# 3_waffling60-ALPS_mcu.net
KiCad netlist of a schematic drawn in Altium Designer
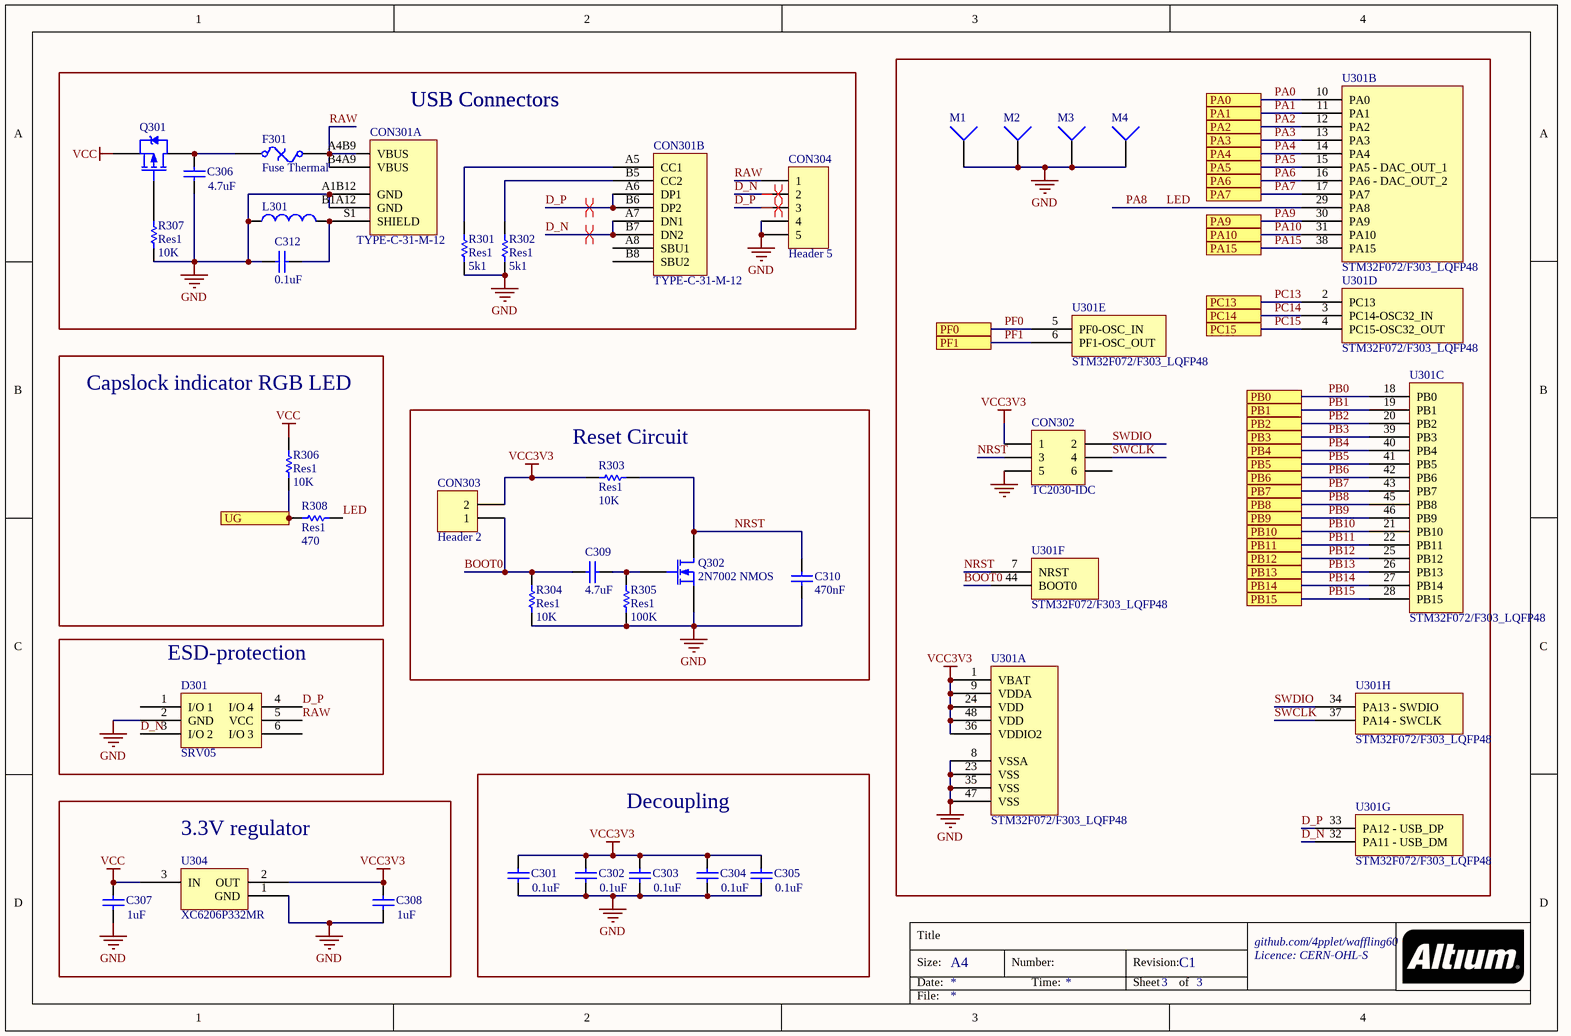
[diagram p0: 3_waffling60-ALPS_mcu.SchDoc]

(export (version "E")
  (design (tool "Eeschema 10.0.6"))
  (components
    (comp (ref "C301")
      (value "0.1uF")
      (footprint "C0603[1608]")
      (description "Capacitor")
      (fields (field (name "LCSC PART #") "C14663") (field (name "MRF.PART") "CC0603KRX7R9BB104"))
      (libsource (lib "Miscellaneous Devices") (part "Cap"))
    )
    (comp (ref "C302")
      (value "0.1uF")
      (footprint "C0603[1608]")
      (description "Capacitor")
      (fields (field (name "LCSC PART #") "C14663") (field (name "MRF.PART") "CC0603KRX7R9BB104"))
      (libsource (lib "Miscellaneous Devices") (part "Cap"))
    )
    (comp (ref "C303")
      (value "0.1uF")
      (footprint "C0603[1608]")
      (description "Capacitor")
      (fields (field (name "LCSC PART #") "C14663") (field (name "MRF.PART") "CC0603KRX7R9BB104"))
      (libsource (lib "Miscellaneous Devices") (part "Cap"))
    )
    (comp (ref "C304")
      (value "0.1uF")
      (footprint "C0603[1608]")
      (description "Capacitor")
      (fields (field (name "LCSC PART #") "C14663") (field (name "MRF.PART") "CC0603KRX7R9BB104"))
      (libsource (lib "Miscellaneous Devices") (part "Cap"))
    )
    (comp (ref "C305")
      (value "0.1uF")
      (footprint "C0603[1608]")
      (description "Capacitor")
      (fields (field (name "LCSC PART #") "C14663") (field (name "MRF.PART") "CC0603KRX7R9BB104"))
      (libsource (lib "Miscellaneous Devices") (part "Cap"))
    )
    (comp (ref "C306")
      (value "4.7uF")
      (footprint "C0603[1608]")
      (description "Capacitor")
      (fields (field (name "LCSC PART #") "C19666") (field (name "MRF.PART") "CL10A475KO8NNNC"))
      (libsource (lib "Miscellaneous Devices") (part "Cap"))
    )
    (comp (ref "C307")
      (value "1uF")
      (footprint "C0603[1608]")
      (description "Capacitor")
      (fields (field (name "LCSC PART #") "C15849") (field (name "MRF.PART") "CL10A105KB8NNNC"))
      (libsource (lib "Miscellaneous Devices") (part "Cap"))
    )
    (comp (ref "C308")
      (value "1uF")
      (footprint "C0603[1608]")
      (description "Capacitor")
      (fields (field (name "LCSC PART #") "C15849") (field (name "MRF.PART") "CL10A105KB8NNNC"))
      (libsource (lib "Miscellaneous Devices") (part "Cap"))
    )
    (comp (ref "C309")
      (value "4.7uF")
      (footprint "C0603[1608]")
      (description "Capacitor")
      (fields (field (name "LCSC PART #") "C19666") (field (name "MRF.PART") "CL10A475KO8NNNC"))
      (libsource (lib "Miscellaneous Devices") (part "Cap"))
    )
    (comp (ref "C310")
      (value "470nF")
      (footprint "C0603[1608]")
      (description "Capacitor")
      (fields (field (name "LCSC PART #") "C1623") (field (name "MRF.PART") "CL10B474KA8NNNC"))
      (libsource (lib "Miscellaneous Devices") (part "Cap"))
    )
    (comp (ref "C312")
      (value "0.1uF")
      (footprint "C0603[1608]")
      (description "Capacitor")
      (fields (field (name "LCSC PART #") "C14663") (field (name "MRF.PART") "CC0603KRX7R9BB104"))
      (libsource (lib "Miscellaneous Devices") (part "Cap"))
    )
    (comp (ref "CON301")
      (value "TYPE-C-31-M-12")
      (footprint "TYPE-C-31-M-12")
      (fields (field (name "LCSC PART #") "C165948"))
      (libsource (lib "Schlib1") (part "TYPE-C-31-M-12"))
    )
    (comp (ref "CON302")
      (value "TC2030-IDC")
      (footprint "TC2030-IDC-NL")
      (description "Header, 3-Pin, Dual row")
      (libsource (lib "Miscellaneous Connectors") (part "Header 3X2"))
    )
    (comp (ref "CON303")
      (value "Header 2")
      (footprint "HDR1X2")
      (description "Header, 2-Pin")
      (libsource (lib "Miscellaneous Connectors") (part "Header 2"))
    )
    (comp (ref "CON304")
      (value "Header 5")
      (footprint "UDB_combo_JST_MOLEX")
      (description "JST for USB daughter board")
      (fields (field (name "LCSC PART #") "C145956"))
      (libsource (lib "Miscellaneous Connectors") (part "Header 5"))
    )
    (comp (ref "D301")
      (value "SRV05")
      (footprint "SOT-23-6")
      (fields (field (name "LCSC PART #") "C85364") (field (name "MRF.PART") "SRV05-4-P-T7"))
      (libsource (lib "Keebs") (part "SRV05"))
    )
    (comp (ref "F301")
      (value "Fuse Thermal")
      (footprint "C1206[3216]")
      (description "Thermal Fuse")
      (fields (field (name "LCSC PART #") "C135338") (field (name "MRF.PART") "ASMD1206-050"))
      (libsource (lib "Miscellaneous Devices") (part "Fuse Thermal"))
    )
    (comp (ref "L301")
      (value "Inductor")
      (footprint "L0805")
      (fields (field (name "LCSC PART #") "C1015") (field (name "MRF.PART") "GZ2012D101TF"))
      (libsource (lib "Simulation Generic Components") (part "Inductor"))
    )
    (comp (ref "M1")
      (value "Socket")
      (footprint "mounting_hole")
      (libsource (lib "Miscellaneous Connectors") (part "Socket"))
    )
    (comp (ref "M2")
      (value "Socket")
      (footprint "mounting_hole")
      (libsource (lib "Miscellaneous Connectors") (part "Socket"))
    )
    (comp (ref "M3")
      (value "Socket")
      (footprint "mounting_hole")
      (libsource (lib "Miscellaneous Connectors") (part "Socket"))
    )
    (comp (ref "M4")
      (value "Socket")
      (footprint "mounting_hole")
      (libsource (lib "Miscellaneous Connectors") (part "Socket"))
    )
    (comp (ref "Q301")
      (value "PMOS-2")
      (footprint "SOT-23-3")
      (description "P-Channel Power MOSFET")
      (fields (field (name "LCSC PART #") "C10487") (field (name "MRF.PART") "SI2301CDS-T1-GE3"))
      (libsource (lib "Miscellaneous Devices") (part "PMOS-2"))
    )
    (comp (ref "Q302")
      (value "2N7002 NMOS")
      (footprint "SOT-23-3")
      (description "N-Channel MOSFET")
      (fields (field (name "LCSC PART #") "C8545") (field (name "MRF.PART") "2N7002"))
      (libsource (lib "Miscellaneous Devices") (part "MOSFET-N"))
    )
    (comp (ref "R301")
      (value "Res1")
      (footprint "R0603[1608]")
      (description "Resistor")
      (fields
        (field (name "ALTIUM_VALUE") "5k1")
        (field (name "LCSC PART #") "C23186")
        (field (name "MRF.PART") "0603WAF5101T5E")
      )
      (libsource (lib "Miscellaneous Devices") (part "Res1"))
    )
    (comp (ref "R302")
      (value "Res1")
      (footprint "R0603[1608]")
      (description "Resistor")
      (fields
        (field (name "ALTIUM_VALUE") "5k1")
        (field (name "LCSC PART #") "C23186")
        (field (name "MRF.PART") "0603WAF5101T5E")
      )
      (libsource (lib "Miscellaneous Devices") (part "Res1"))
    )
    (comp (ref "R303")
      (value "Res1")
      (footprint "R0603[1608]")
      (description "Resistor")
      (fields
        (field (name "ALTIUM_VALUE") "10K")
        (field (name "LCSC PART #") "C25804")
        (field (name "MRF.PART") "0603WAF1002T5E")
      )
      (libsource (lib "Miscellaneous Devices") (part "Res1"))
    )
    (comp (ref "R304")
      (value "Res1")
      (footprint "R0603[1608]")
      (description "Resistor")
      (fields
        (field (name "ALTIUM_VALUE") "10K")
        (field (name "LCSC PART #") "C25804")
        (field (name "MRF.PART") "0603WAF1002T5E")
      )
      (libsource (lib "Miscellaneous Devices") (part "Res1"))
    )
    (comp (ref "R305")
      (value "Res1")
      (footprint "R0603[1608]")
      (description "Resistor")
      (fields
        (field (name "ALTIUM_VALUE") "100K")
        (field (name "LCSC PART #") "C25803")
        (field (name "MRF.PART") "0603WAF1003T5E")
      )
      (libsource (lib "Miscellaneous Devices") (part "Res1"))
    )
    (comp (ref "R306")
      (value "Res1")
      (footprint "R0603[1608]")
      (description "Resistor")
      (fields
        (field (name "ALTIUM_VALUE") "10K")
        (field (name "LCSC PART #") "C25804")
        (field (name "MRF.PART") "0603WAF1002T5E")
      )
      (libsource (lib "Miscellaneous Devices") (part "Res1"))
    )
    (comp (ref "R307")
      (value "Res1")
      (footprint "R0603[1608]")
      (description "Resistor")
      (fields
        (field (name "ALTIUM_VALUE") "10K")
        (field (name "LCSC PART #") "C25804")
        (field (name "MRF.PART") "0603WAF1002T5E")
      )
      (libsource (lib "Miscellaneous Devices") (part "Res1"))
    )
    (comp (ref "R308")
      (value "Res1")
      (footprint "R0603[1608]")
      (description "Resistor")
      (fields
        (field (name "ALTIUM_VALUE") "470")
        (field (name "LCSC PART #") "C23179")
        (field (name "MRF.PART") "0603WAF4700T5E")
      )
      (libsource (lib "Miscellaneous Devices") (part "Res1"))
    )
    (comp (ref "U301")
      (value "STM32F072/F303_LQFP48")
      (footprint "STM32 - COMBO 7X7MM")
      (fields (field (name "LCSC PART #") "C915660") (field (name "MRF.PART") "APM32F072CBT6"))
      (libsource (lib "Keebs") (part "STM32F072/F303_LQFP48"))
    )
    (comp (ref "U304")
      (value "XC6206P332MR")
      (footprint "SOT-23-3")
      (fields (field (name "LCSC PART #") "C5446"))
      (libsource (lib "Keebs") (part "SOT23 LDO"))
    )
  )
  (nets
    (net (code "1") (name "/BOOT0") (class "Default")
      (node (ref "C309") (pin "1") (pinfunction "1_1") (pintype "passive"))
      (node (ref "CON303") (pin "1") (pinfunction "1_1") (pintype "passive"))
      (node (ref "R304") (pin "1") (pinfunction "1_1") (pintype "passive"))
      (node (ref "U301") (pin "44") (pinfunction "BOOT0_44") (pintype "passive"))
    )
    (net (code "2") (name "/D_N") (class "Default")
      (node (ref "CON301") (pin "A7") (pinfunction "DN1_A7") (pintype "passive"))
      (node (ref "CON301") (pin "B7") (pinfunction "DN2_B7") (pintype "passive"))
      (node (ref "CON304") (pin "2") (pinfunction "2_2") (pintype "passive"))
      (node (ref "D301") (pin "3") (pinfunction "I/O_2_3") (pintype "passive"))
      (node (ref "U301") (pin "32") (pinfunction "PA11_-_USB_DM_32") (pintype "passive"))
    )
    (net (code "3") (name "/D_P") (class "Default")
      (node (ref "CON301") (pin "A6") (pinfunction "DP1_A6") (pintype "passive"))
      (node (ref "CON301") (pin "B6") (pinfunction "DP2_B6") (pintype "passive"))
      (node (ref "CON304") (pin "3") (pinfunction "3_3") (pintype "passive"))
      (node (ref "D301") (pin "4") (pinfunction "I/O_4_4") (pintype "passive"))
      (node (ref "U301") (pin "33") (pinfunction "PA12_-_USB_DP_33") (pintype "passive"))
    )
    (net (code "4") (name "/LED") (class "Default")
      (node (ref "R308") (pin "2") (pinfunction "2_2") (pintype "passive"))
      (node (ref "U301") (pin "29") (pinfunction "PA8_29") (pintype "passive"))
    )
    (net (code "5") (name "/NRST") (class "Default")
      (node (ref "C310") (pin "1") (pinfunction "1_1") (pintype "passive"))
      (node (ref "CON302") (pin "3") (pinfunction "3_3") (pintype "passive"))
      (node (ref "Q302") (pin "3") (pinfunction "D_3") (pintype "passive"))
      (node (ref "R303") (pin "2") (pinfunction "2_2") (pintype "passive"))
      (node (ref "U301") (pin "7") (pinfunction "NRST_7") (pintype "passive"))
    )
    (net (code "6") (name "/PA0") (class "Default")
      (node (ref "U301") (pin "10") (pinfunction "PA0_10") (pintype "passive"))
    )
    (net (code "7") (name "/PA1") (class "Default")
      (node (ref "U301") (pin "11") (pinfunction "PA1_11") (pintype "passive"))
    )
    (net (code "8") (name "/PA2") (class "Default")
      (node (ref "U301") (pin "12") (pinfunction "PA2_12") (pintype "passive"))
    )
    (net (code "9") (name "/PA3") (class "Default")
      (node (ref "U301") (pin "13") (pinfunction "PA3_13") (pintype "passive"))
    )
    (net (code "10") (name "/PA4") (class "Default")
      (node (ref "U301") (pin "14") (pinfunction "PA4_14") (pintype "passive"))
    )
    (net (code "11") (name "/PA5") (class "Default")
      (node (ref "U301") (pin "15") (pinfunction "PA5_-_DAC_OUT_1_15") (pintype "passive"))
    )
    (net (code "12") (name "/PA6") (class "Default")
      (node (ref "U301") (pin "16") (pinfunction "PA6_-_DAC_OUT_2_16") (pintype "passive"))
    )
    (net (code "13") (name "/PA7") (class "Default")
      (node (ref "U301") (pin "17") (pinfunction "PA7_17") (pintype "passive"))
    )
    (net (code "14") (name "/PA9") (class "Default")
      (node (ref "U301") (pin "30") (pinfunction "PA9_30") (pintype "passive"))
    )
    (net (code "15") (name "/PA10") (class "Default")
      (node (ref "U301") (pin "31") (pinfunction "PA10_31") (pintype "passive"))
    )
    (net (code "16") (name "/PA15") (class "Default")
      (node (ref "U301") (pin "38") (pinfunction "PA15_38") (pintype "passive"))
    )
    (net (code "17") (name "/PB0") (class "Default")
      (node (ref "U301") (pin "18") (pinfunction "PB0_18") (pintype "passive"))
    )
    (net (code "18") (name "/PB1") (class "Default")
      (node (ref "U301") (pin "19") (pinfunction "PB1_19") (pintype "passive"))
    )
    (net (code "19") (name "/PB2") (class "Default")
      (node (ref "U301") (pin "20") (pinfunction "PB2_20") (pintype "passive"))
    )
    (net (code "20") (name "/PB3") (class "Default")
      (node (ref "U301") (pin "39") (pinfunction "PB3_39") (pintype "passive"))
    )
    (net (code "21") (name "/PB4") (class "Default")
      (node (ref "U301") (pin "40") (pinfunction "PB4_40") (pintype "passive"))
    )
    (net (code "22") (name "/PB5") (class "Default")
      (node (ref "U301") (pin "41") (pinfunction "PB5_41") (pintype "passive"))
    )
    (net (code "23") (name "/PB6") (class "Default")
      (node (ref "U301") (pin "42") (pinfunction "PB6_42") (pintype "passive"))
    )
    (net (code "24") (name "/PB7") (class "Default")
      (node (ref "U301") (pin "43") (pinfunction "PB7_43") (pintype "passive"))
    )
    (net (code "25") (name "/PB8") (class "Default")
      (node (ref "U301") (pin "45") (pinfunction "PB8_45") (pintype "passive"))
    )
    (net (code "26") (name "/PB9") (class "Default")
      (node (ref "U301") (pin "46") (pinfunction "PB9_46") (pintype "passive"))
    )
    (net (code "27") (name "/PB10") (class "Default")
      (node (ref "U301") (pin "21") (pinfunction "PB10_21") (pintype "passive"))
    )
    (net (code "28") (name "/PB11") (class "Default")
      (node (ref "U301") (pin "22") (pinfunction "PB11_22") (pintype "passive"))
    )
    (net (code "29") (name "/PB12") (class "Default")
      (node (ref "U301") (pin "25") (pinfunction "PB12_25") (pintype "passive"))
    )
    (net (code "30") (name "/PB13") (class "Default")
      (node (ref "U301") (pin "26") (pinfunction "PB13_26") (pintype "passive"))
    )
    (net (code "31") (name "/PB14") (class "Default")
      (node (ref "U301") (pin "27") (pinfunction "PB14_27") (pintype "passive"))
    )
    (net (code "32") (name "/PB15") (class "Default")
      (node (ref "U301") (pin "28") (pinfunction "PB15_28") (pintype "passive"))
    )
    (net (code "33") (name "/PC13") (class "Default")
      (node (ref "U301") (pin "2") (pinfunction "PC13_2") (pintype "passive"))
    )
    (net (code "34") (name "/PC14") (class "Default")
      (node (ref "U301") (pin "3") (pinfunction "PC14-OSC32_IN_3") (pintype "passive"))
    )
    (net (code "35") (name "/PC15") (class "Default")
      (node (ref "U301") (pin "4") (pinfunction "PC15-OSC32_OUT_4") (pintype "passive"))
    )
    (net (code "36") (name "/PF0") (class "Default")
      (node (ref "U301") (pin "5") (pinfunction "PF0-OSC_IN_5") (pintype "passive"))
    )
    (net (code "37") (name "/PF1") (class "Default")
      (node (ref "U301") (pin "6") (pinfunction "PF1-OSC_OUT_6") (pintype "passive"))
    )
    (net (code "38") (name "/RAW") (class "Default")
      (node (ref "CON301") (pin "A4B9") (pinfunction "VBUS_A4B9") (pintype "passive"))
      (node (ref "CON301") (pin "B4A9") (pinfunction "VBUS_B4A9") (pintype "passive"))
      (node (ref "CON304") (pin "1") (pinfunction "1_1") (pintype "passive"))
      (node (ref "D301") (pin "5") (pinfunction "VCC_5") (pintype "passive"))
      (node (ref "F301") (pin "2") (pinfunction "2_2") (pintype "passive"))
    )
    (net (code "39") (name "/SWCLK") (class "Default")
      (node (ref "CON302") (pin "4") (pinfunction "4_4") (pintype "passive"))
      (node (ref "U301") (pin "37") (pinfunction "PA14_-_SWCLK_37") (pintype "passive"))
    )
    (net (code "40") (name "/SWDIO") (class "Default")
      (node (ref "CON302") (pin "2") (pinfunction "2_2") (pintype "passive"))
      (node (ref "U301") (pin "34") (pinfunction "PA13_-_SWDIO_34") (pintype "passive"))
    )
    (net (code "41") (name "/UG") (class "Default")
      (node (ref "R306") (pin "2") (pinfunction "2_2") (pintype "passive"))
      (node (ref "R308") (pin "1") (pinfunction "1_1") (pintype "passive"))
    )
    (net (code "42") (name "GND") (class "Default")
      (node (ref "C301") (pin "1") (pinfunction "1_1") (pintype "passive"))
      (node (ref "C302") (pin "1") (pinfunction "1_1") (pintype "passive"))
      (node (ref "C303") (pin "1") (pinfunction "1_1") (pintype "passive"))
      (node (ref "C304") (pin "1") (pinfunction "1_1") (pintype "passive"))
      (node (ref "C305") (pin "1") (pinfunction "1_1") (pintype "passive"))
      (node (ref "C306") (pin "1") (pinfunction "1_1") (pintype "passive"))
      (node (ref "C307") (pin "1") (pinfunction "1_1") (pintype "passive"))
      (node (ref "C308") (pin "1") (pinfunction "1_1") (pintype "passive"))
      (node (ref "C310") (pin "2") (pinfunction "2_2") (pintype "passive"))
      (node (ref "C312") (pin "1") (pinfunction "1_1") (pintype "passive"))
      (node (ref "CON301") (pin "A1B12") (pinfunction "GND_A1B12") (pintype "passive"))
      (node (ref "CON301") (pin "B1A12") (pinfunction "GND_B1A12") (pintype "passive"))
      (node (ref "CON302") (pin "5") (pinfunction "5_5") (pintype "passive"))
      (node (ref "CON304") (pin "4") (pinfunction "4_4") (pintype "passive"))
      (node (ref "CON304") (pin "5") (pinfunction "5_5") (pintype "passive"))
      (node (ref "D301") (pin "2") (pinfunction "GND_2") (pintype "passive"))
      (node (ref "L301") (pin "1") (pinfunction "1_1") (pintype "passive"))
      (node (ref "M1") (pin "1") (pinfunction "1_1") (pintype "passive"))
      (node (ref "M2") (pin "1") (pinfunction "1_1") (pintype "passive"))
      (node (ref "M3") (pin "1") (pinfunction "1_1") (pintype "passive"))
      (node (ref "M4") (pin "1") (pinfunction "1_1") (pintype "passive"))
      (node (ref "Q302") (pin "2") (pinfunction "S_2") (pintype "passive"))
      (node (ref "R301") (pin "2") (pinfunction "2_2") (pintype "passive"))
      (node (ref "R302") (pin "2") (pinfunction "2_2") (pintype "passive"))
      (node (ref "R304") (pin "2") (pinfunction "2_2") (pintype "passive"))
      (node (ref "R305") (pin "2") (pinfunction "2_2") (pintype "passive"))
      (node (ref "R307") (pin "2") (pinfunction "2_2") (pintype "passive"))
      (node (ref "U301") (pin "23") (pinfunction "VSS_23") (pintype "passive"))
      (node (ref "U301") (pin "35") (pinfunction "VSS_35") (pintype "passive"))
      (node (ref "U301") (pin "47") (pinfunction "VSS_47") (pintype "passive"))
      (node (ref "U301") (pin "8") (pinfunction "VSSA_8") (pintype "passive"))
      (node (ref "U304") (pin "1") (pinfunction "GND_1") (pintype "passive"))
    )
    (net (code "43") (name "Net-(CON301A-SHIELD)") (class "Default")
      (node (ref "C312") (pin "2") (pinfunction "2_2") (pintype "passive"))
      (node (ref "CON301") (pin "S1") (pinfunction "SHIELD_S1") (pintype "passive"))
      (node (ref "L301") (pin "2") (pinfunction "2_2") (pintype "passive"))
    )
    (net (code "44") (name "Net-(CON301B-CC1)") (class "Default")
      (node (ref "CON301") (pin "A5") (pinfunction "CC1_A5") (pintype "passive"))
      (node (ref "R301") (pin "1") (pinfunction "1_1") (pintype "passive"))
    )
    (net (code "45") (name "Net-(CON301B-CC2)") (class "Default")
      (node (ref "CON301") (pin "B5") (pinfunction "CC2_B5") (pintype "passive"))
      (node (ref "R302") (pin "1") (pinfunction "1_1") (pintype "passive"))
    )
    (net (code "46") (name "Net-(Q301-D)") (class "Default")
      (node (ref "C306") (pin "2") (pinfunction "2_2") (pintype "passive"))
      (node (ref "F301") (pin "1") (pinfunction "1_1") (pintype "passive"))
      (node (ref "Q301") (pin "3") (pinfunction "D_3") (pintype "passive"))
    )
    (net (code "47") (name "Net-(Q301-G)") (class "Default")
      (node (ref "Q301") (pin "1") (pinfunction "G_1") (pintype "passive"))
      (node (ref "R307") (pin "1") (pinfunction "1_1") (pintype "passive"))
    )
    (net (code "48") (name "Net-(Q302-G)") (class "Default")
      (node (ref "C309") (pin "2") (pinfunction "2_2") (pintype "passive"))
      (node (ref "Q302") (pin "1") (pinfunction "G_1") (pintype "passive"))
      (node (ref "R305") (pin "1") (pinfunction "1_1") (pintype "passive"))
    )
    (net (code "49") (name "VCC") (class "Default")
      (node (ref "C307") (pin "2") (pinfunction "2_2") (pintype "passive"))
      (node (ref "Q301") (pin "2") (pinfunction "S_2") (pintype "passive"))
      (node (ref "R306") (pin "1") (pinfunction "1_1") (pintype "passive"))
      (node (ref "U304") (pin "3") (pinfunction "IN_3") (pintype "passive"))
    )
    (net (code "50") (name "VCC3V3") (class "Default")
      (node (ref "C301") (pin "2") (pinfunction "2_2") (pintype "passive"))
      (node (ref "C302") (pin "2") (pinfunction "2_2") (pintype "passive"))
      (node (ref "C303") (pin "2") (pinfunction "2_2") (pintype "passive"))
      (node (ref "C304") (pin "2") (pinfunction "2_2") (pintype "passive"))
      (node (ref "C305") (pin "2") (pinfunction "2_2") (pintype "passive"))
      (node (ref "C308") (pin "2") (pinfunction "2_2") (pintype "passive"))
      (node (ref "CON302") (pin "1") (pinfunction "1_1") (pintype "passive"))
      (node (ref "CON303") (pin "2") (pinfunction "2_2") (pintype "passive"))
      (node (ref "R303") (pin "1") (pinfunction "1_1") (pintype "passive"))
      (node (ref "U301") (pin "1") (pinfunction "VBAT_1") (pintype "passive"))
      (node (ref "U301") (pin "24") (pinfunction "VDD_24") (pintype "passive"))
      (node (ref "U301") (pin "36") (pinfunction "VDDIO2_36") (pintype "passive"))
      (node (ref "U301") (pin "48") (pinfunction "VDD_48") (pintype "passive"))
      (node (ref "U301") (pin "9") (pinfunction "VDDA_9") (pintype "passive"))
      (node (ref "U304") (pin "2") (pinfunction "OUT_2") (pintype "passive"))
    )
    (net (code "51") (name "unconnected-(CON301B-SBU1-PadA8)") (class "Default")
      (node (ref "CON301") (pin "A8") (pinfunction "SBU1_A8") (pintype "passive"))
    )
    (net (code "52") (name "unconnected-(CON301B-SBU2-PadB8)") (class "Default")
      (node (ref "CON301") (pin "B8") (pinfunction "SBU2_B8") (pintype "passive"))
    )
    (net (code "53") (name "unconnected-(CON302-Pad6)") (class "Default")
      (node (ref "CON302") (pin "6") (pinfunction "6_6") (pintype "passive"))
    )
    (net (code "54") (name "unconnected-(D301-I{slash}O_1-Pad1)") (class "Default")
      (node (ref "D301") (pin "1") (pinfunction "I/O_1_1") (pintype "passive"))
    )
    (net (code "55") (name "unconnected-(D301-I{slash}O_3-Pad6)") (class "Default")
      (node (ref "D301") (pin "6") (pinfunction "I/O_3_6") (pintype "passive"))
    )
  )
)
